# FYP_POWERBOARD_60V100A_REV2.net
KiCad netlist of a schematic drawn in Altium Designer
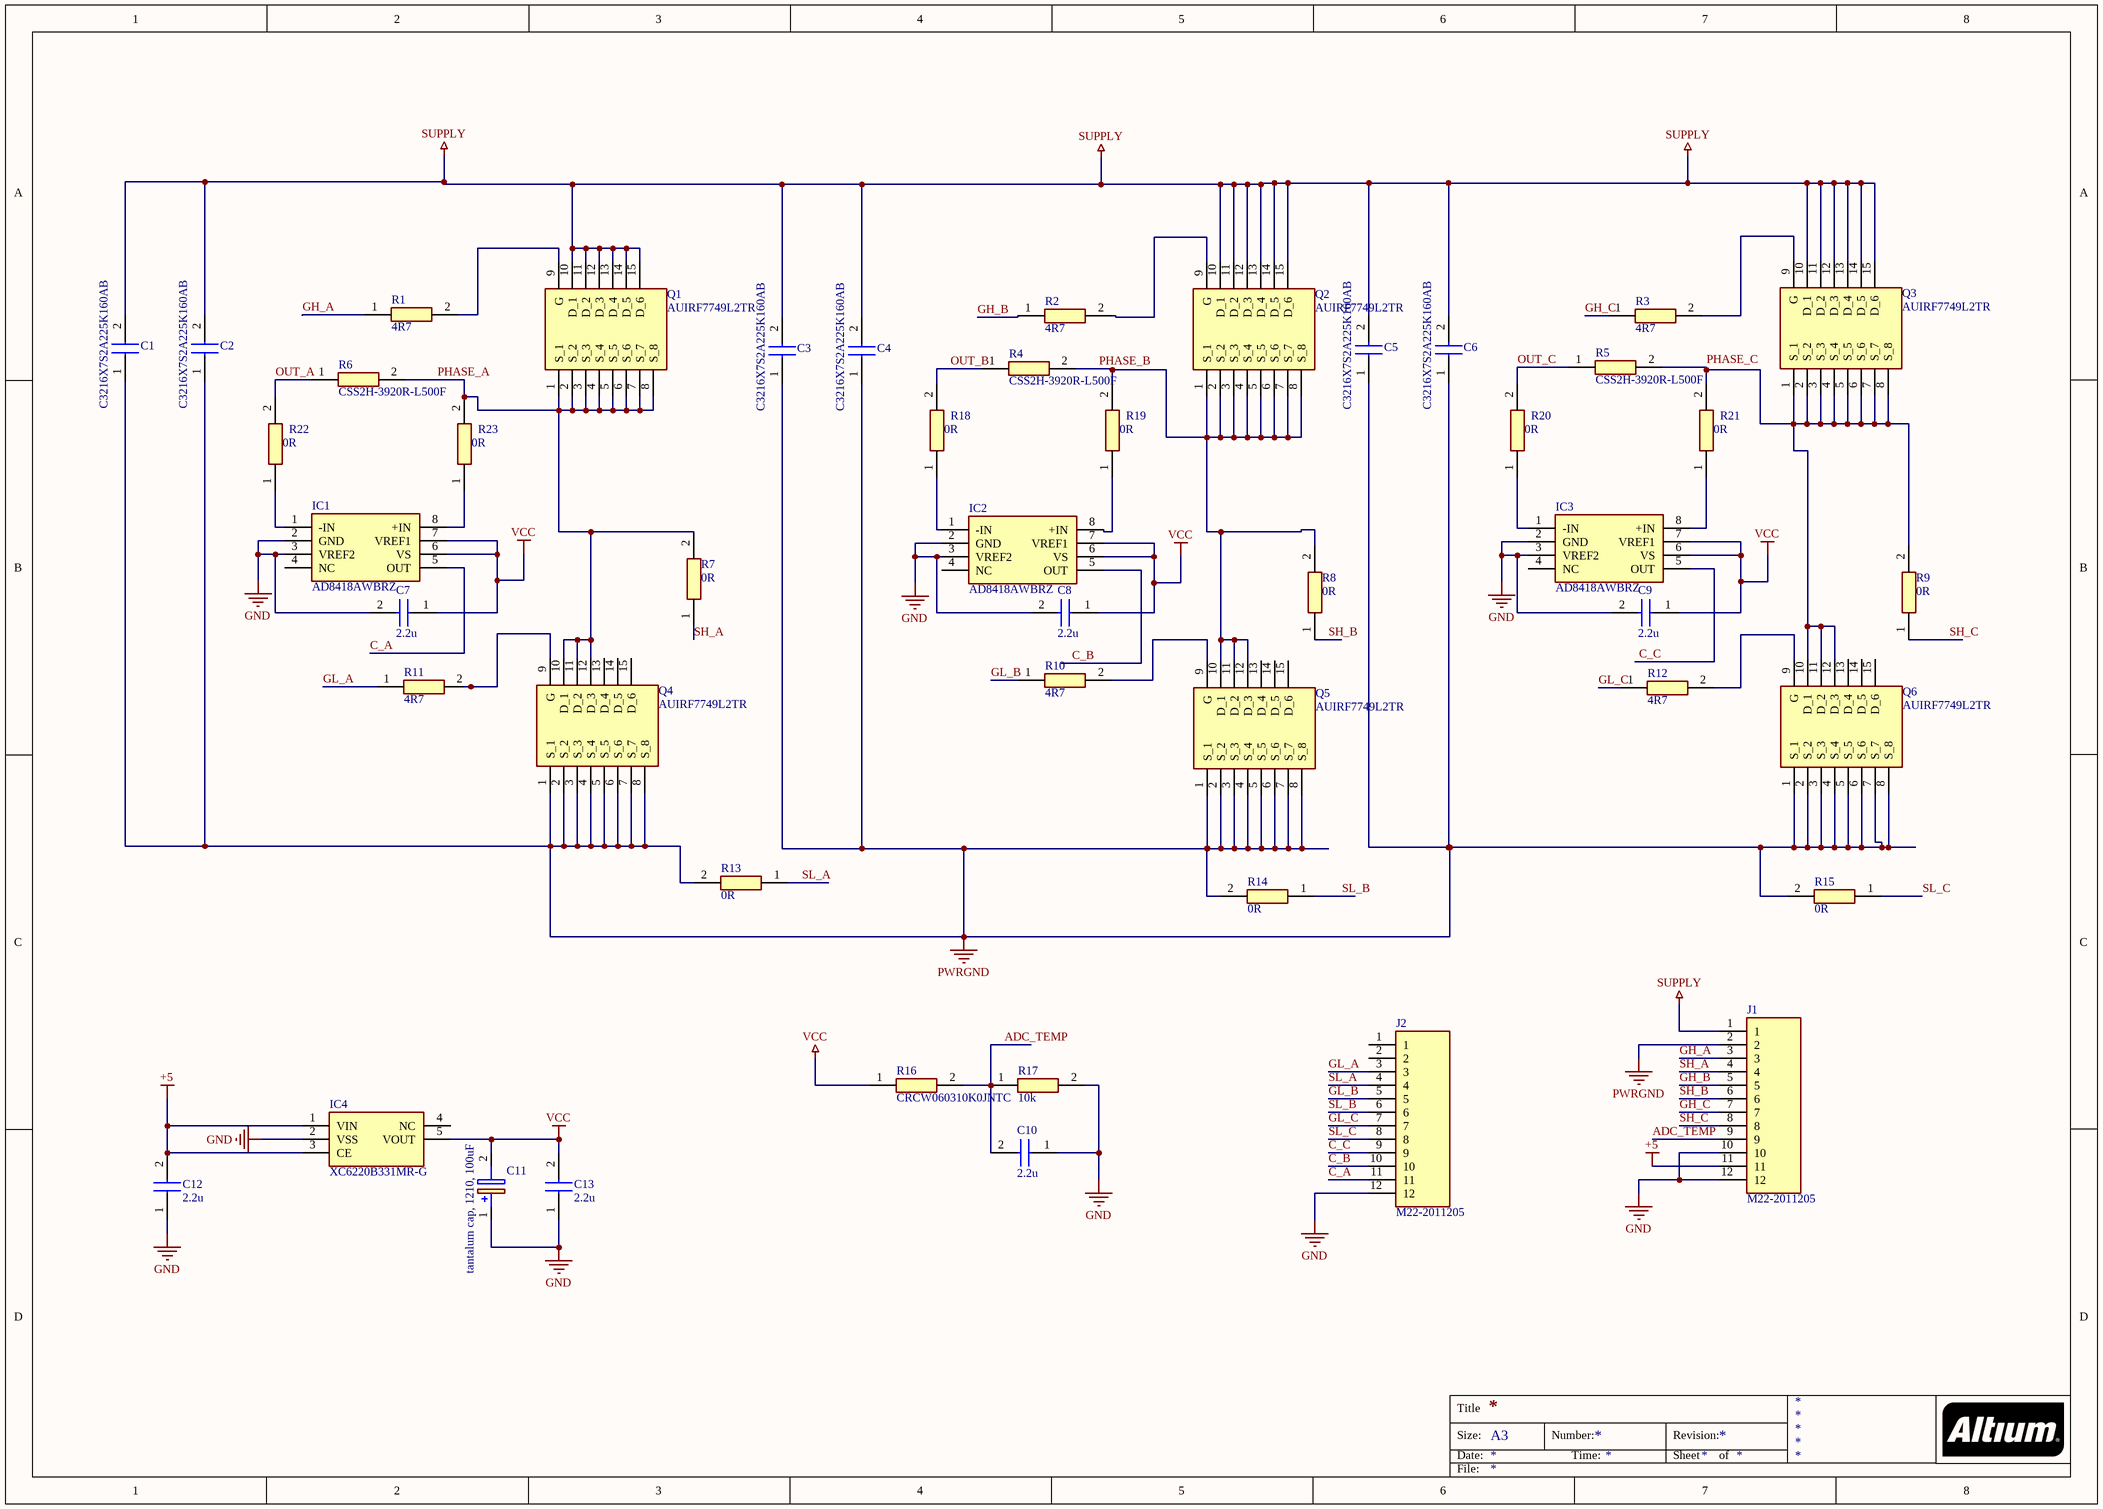
[diagram p0: FYP_POWERBOARD_60V100A_REV2.SchDoc]

(export (version "E")
  (design (tool "Eeschema 10.0.6"))
  (components
    (comp (ref "C1")
      (value "C3216X7S2A225K160AB")
      (footprint "SamacSys:CAPC3216X180N")
      (description "Capacitor")
      (fields
        (field (name "MOUSER PART NUMBER") "810-C3216X7S2A225K")
        (field (name "RS PART NUMBER") "7883079P")
      )
      (libsource (lib "*") (part "C3216X7S2A225K160AB"))
    )
    (comp (ref "C2")
      (value "C3216X7S2A225K160AB")
      (footprint "SamacSys:CAPC3216X180N")
      (description "Capacitor")
      (fields
        (field (name "MOUSER PART NUMBER") "810-C3216X7S2A225K")
        (field (name "RS PART NUMBER") "7883079P")
      )
      (libsource (lib "*") (part "C3216X7S2A225K160AB"))
    )
    (comp (ref "C3")
      (value "C3216X7S2A225K160AB")
      (footprint "SamacSys:CAPC3216X180N")
      (description "Capacitor")
      (fields
        (field (name "MOUSER PART NUMBER") "810-C3216X7S2A225K")
        (field (name "RS PART NUMBER") "7883079P")
      )
      (libsource (lib "*") (part "C3216X7S2A225K160AB"))
    )
    (comp (ref "C4")
      (value "C3216X7S2A225K160AB")
      (footprint "SamacSys:CAPC3216X180N")
      (description "Capacitor")
      (fields
        (field (name "MOUSER PART NUMBER") "810-C3216X7S2A225K")
        (field (name "RS PART NUMBER") "7883079P")
      )
      (libsource (lib "*") (part "C3216X7S2A225K160AB"))
    )
    (comp (ref "C5")
      (value "C3216X7S2A225K160AB")
      (footprint "SamacSys:CAPC3216X180N")
      (description "Capacitor")
      (fields
        (field (name "MOUSER PART NUMBER") "810-C3216X7S2A225K")
        (field (name "RS PART NUMBER") "7883079P")
      )
      (libsource (lib "*") (part "C3216X7S2A225K160AB"))
    )
    (comp (ref "C6")
      (value "C3216X7S2A225K160AB")
      (footprint "SamacSys:CAPC3216X180N")
      (description "Capacitor")
      (fields
        (field (name "MOUSER PART NUMBER") "810-C3216X7S2A225K")
        (field (name "RS PART NUMBER") "7883079P")
      )
      (libsource (lib "*") (part "C3216X7S2A225K160AB"))
    )
    (comp (ref "C7")
      (value "2.2u")
      (footprint "SamacSys:CAPC1608X90N")
      (description "Capacitor")
      (fields
        (field (name "MANUFACTURER_PART_NUMBER") "GCM188R70J225KE22D")
        (field (name "MOUSER PART NUMBER") "81-GCM188R70J225KE2D")
      )
      (libsource (lib "*") (part "GCM188R70J225KE22D"))
    )
    (comp (ref "C8")
      (value "2.2u")
      (footprint "SamacSys:CAPC1608X90N")
      (description "Capacitor")
      (fields
        (field (name "MANUFACTURER_PART_NUMBER") "GCM188R70J225KE22D")
        (field (name "MOUSER PART NUMBER") "81-GCM188R70J225KE2D")
      )
      (libsource (lib "*") (part "GCM188R70J225KE22D"))
    )
    (comp (ref "C9")
      (value "2.2u")
      (footprint "SamacSys:CAPC1608X90N")
      (description "Capacitor")
      (fields
        (field (name "MANUFACTURER_PART_NUMBER") "GCM188R70J225KE22D")
        (field (name "MOUSER PART NUMBER") "81-GCM188R70J225KE2D")
      )
      (libsource (lib "*") (part "GCM188R70J225KE22D"))
    )
    (comp (ref "C10")
      (value "2.2u")
      (footprint "SamacSys:CAPC1608X90N")
      (description "Capacitor")
      (fields
        (field (name "MANUFACTURER_PART_NUMBER") "GCM188R70J225KE22D")
        (field (name "MOUSER PART NUMBER") "81-GCM188R70J225KE2D")
      )
      (libsource (lib "*") (part "GCM188R70J225KE22D"))
    )
    (comp (ref "C11")
      (value "tantalum cap, 1210, 100uF")
      (footprint "SamacSys:CAPPM3528X210N")
      (description "Capacitor Polarised")
      (fields (field (name "MANUFACTURER_PART_NUMBER") "293D107X06R3B2TE3"))
      (libsource (lib "*") (part "293D107X06R3B2TE3"))
    )
    (comp (ref "C12")
      (value "2.2u")
      (footprint "SamacSys:CAPC1608X90N")
      (description "Capacitor")
      (fields
        (field (name "MANUFACTURER_PART_NUMBER") "GCM188R70J225KE22D")
        (field (name "MOUSER PART NUMBER") "81-GCM188R70J225KE2D")
      )
      (libsource (lib "*") (part "GCM188R70J225KE22D"))
    )
    (comp (ref "C13")
      (value "2.2u")
      (footprint "SamacSys:CAPC1608X90N")
      (description "Capacitor")
      (fields
        (field (name "MANUFACTURER_PART_NUMBER") "GCM188R70J225KE22D")
        (field (name "MOUSER PART NUMBER") "81-GCM188R70J225KE2D")
      )
      (libsource (lib "*") (part "GCM188R70J225KE22D"))
    )
    (comp (ref "IC1")
      (value "AD8418AWBRZ")
      (footprint "SamacSys:SOP65P490X110-8N")
      (description "Integrated Circuit")
      (fields (field (name "MOUSER PART NUMBER") "584-AD8418AWBRZ") (field (name "RS PART NUMBER") "7989903"))
      (libsource (lib "SamacSys") (part "AD8418AWBRZ"))
    )
    (comp (ref "IC2")
      (value "AD8418AWBRZ")
      (footprint "SamacSys:SOP65P490X110-8N")
      (description "Integrated Circuit")
      (fields (field (name "MOUSER PART NUMBER") "584-AD8418AWBRZ") (field (name "RS PART NUMBER") "7989903"))
      (libsource (lib "SamacSys") (part "AD8418AWBRZ"))
    )
    (comp (ref "IC3")
      (value "AD8418AWBRZ")
      (footprint "SamacSys:SOP65P490X110-8N")
      (description "Integrated Circuit")
      (fields (field (name "MOUSER PART NUMBER") "584-AD8418AWBRZ") (field (name "RS PART NUMBER") "7989903"))
      (libsource (lib "SamacSys") (part "AD8418AWBRZ"))
    )
    (comp (ref "IC4")
      (value "XC6220B331MR-G")
      (footprint "SamacSys:SOT95P280X120-5N")
      (description "Integrated Circuit")
      (fields (field (name "MOUSER PART NUMBER") "865-XC6220B331MR-G"))
      (libsource (lib "*") (part "XC6220B331MR-G"))
    )
    (comp (ref "J1")
      (value "M22-2011205")
      (footprint "SamacSys:HDRV12W60P0X200_1X12_2415X200X525P")
      (description "Connector")
      (fields (field (name "MOUSER PART NUMBER") "855-M22-2011205") (field (name "RS PART NUMBER") "1730943"))
      (libsource (lib "*") (part "M22-2011205"))
    )
    (comp (ref "J2")
      (value "M22-2011205")
      (footprint "SamacSys:HDRV12W60P0X200_1X12_2415X200X525P")
      (description "Connector")
      (fields (field (name "MOUSER PART NUMBER") "855-M22-2011205") (field (name "RS PART NUMBER") "1730943"))
      (libsource (lib "*") (part "M22-2011205"))
    )
    (comp (ref "Q1")
      (value "AUIRF7749L2TR")
      (footprint "SamacSys:IRF7749L2TRPBF")
      (description "MOSFET (N-Channel)")
      (fields (field (name "MOUSER PART NUMBER") "942-AUIRF7749L2TR"))
      (libsource (lib "*") (part "AUIRF7749L2TR"))
    )
    (comp (ref "Q2")
      (value "AUIRF7749L2TR")
      (footprint "SamacSys:IRF7749L2TRPBF")
      (description "MOSFET (N-Channel)")
      (fields (field (name "MOUSER PART NUMBER") "942-AUIRF7749L2TR"))
      (libsource (lib "*") (part "AUIRF7749L2TR"))
    )
    (comp (ref "Q3")
      (value "AUIRF7749L2TR")
      (footprint "SamacSys:IRF7749L2TRPBF")
      (description "MOSFET (N-Channel)")
      (fields (field (name "MOUSER PART NUMBER") "942-AUIRF7749L2TR"))
      (libsource (lib "*") (part "AUIRF7749L2TR"))
    )
    (comp (ref "Q4")
      (value "AUIRF7749L2TR")
      (footprint "SamacSys:IRF7749L2TRPBF")
      (description "MOSFET (N-Channel)")
      (fields (field (name "MOUSER PART NUMBER") "942-AUIRF7749L2TR"))
      (libsource (lib "*") (part "AUIRF7749L2TR"))
    )
    (comp (ref "Q5")
      (value "AUIRF7749L2TR")
      (footprint "SamacSys:IRF7749L2TRPBF")
      (description "MOSFET (N-Channel)")
      (fields (field (name "MOUSER PART NUMBER") "942-AUIRF7749L2TR"))
      (libsource (lib "*") (part "AUIRF7749L2TR"))
    )
    (comp (ref "Q6")
      (value "AUIRF7749L2TR")
      (footprint "SamacSys:IRF7749L2TRPBF")
      (description "MOSFET (N-Channel)")
      (fields (field (name "MOUSER PART NUMBER") "942-AUIRF7749L2TR"))
      (libsource (lib "*") (part "AUIRF7749L2TR"))
    )
    (comp (ref "R1")
      (value "4R7")
      (footprint "SamacSys:RESC1608X55N")
      (description "Resistor")
      (fields
        (field (name "MANUFACTURER_PART_NUMBER") "CPF0603B100RE")
        (field (name "MOUSER PART NUMBER") "279-CPF0603B100RE")
      )
      (libsource (lib "") (part "CPF0603B100RE_1"))
    )
    (comp (ref "R2")
      (value "4R7")
      (footprint "SamacSys:RESC1608X55N")
      (description "Resistor")
      (fields
        (field (name "MANUFACTURER_PART_NUMBER") "CPF0603B100RE")
        (field (name "MOUSER PART NUMBER") "279-CPF0603B100RE")
      )
      (libsource (lib "") (part "CPF0603B100RE_1"))
    )
    (comp (ref "R3")
      (value "4R7")
      (footprint "SamacSys:RESC1608X55N")
      (description "Resistor")
      (fields
        (field (name "MANUFACTURER_PART_NUMBER") "CPF0603B100RE")
        (field (name "MOUSER PART NUMBER") "279-CPF0603B100RE")
      )
      (libsource (lib "") (part "CPF0603B100RE_1"))
    )
    (comp (ref "R4")
      (value "CSS2H-3920R-L500F")
      (footprint "SamacSys:RESC10052X137N")
      (description "Resistor")
      (fields
        (field (name "MOUSER PART NUMBER") "652-CSS2H3920RL500F")
        (field (name "RS PART NUMBER") "1348150")
      )
      (libsource (lib "*") (part "CSS2H-3920R-L500F"))
    )
    (comp (ref "R5")
      (value "CSS2H-3920R-L500F")
      (footprint "SamacSys:RESC10052X137N")
      (description "Resistor")
      (fields
        (field (name "MOUSER PART NUMBER") "652-CSS2H3920RL500F")
        (field (name "RS PART NUMBER") "1348150")
      )
      (libsource (lib "*") (part "CSS2H-3920R-L500F"))
    )
    (comp (ref "R6")
      (value "CSS2H-3920R-L500F")
      (footprint "SamacSys:RESC10052X137N")
      (description "Resistor")
      (fields
        (field (name "MOUSER PART NUMBER") "652-CSS2H3920RL500F")
        (field (name "RS PART NUMBER") "1348150")
      )
      (libsource (lib "*") (part "CSS2H-3920R-L500F"))
    )
    (comp (ref "R7")
      (value "0R")
      (footprint "SamacSys:RESC1608X55N")
      (description "Resistor")
      (fields
        (field (name "MANUFACTURER_PART_NUMBER") "CPF0603B100RE")
        (field (name "MOUSER PART NUMBER") "279-CPF0603B100RE")
      )
      (libsource (lib "") (part "CPF0603B100RE_2"))
    )
    (comp (ref "R8")
      (value "0R")
      (footprint "SamacSys:RESC1608X55N")
      (description "Resistor")
      (fields
        (field (name "MANUFACTURER_PART_NUMBER") "CPF0603B100RE")
        (field (name "MOUSER PART NUMBER") "279-CPF0603B100RE")
      )
      (libsource (lib "") (part "CPF0603B100RE_2"))
    )
    (comp (ref "R9")
      (value "0R")
      (footprint "SamacSys:RESC1608X55N")
      (description "Resistor")
      (fields
        (field (name "MANUFACTURER_PART_NUMBER") "CPF0603B100RE")
        (field (name "MOUSER PART NUMBER") "279-CPF0603B100RE")
      )
      (libsource (lib "") (part "CPF0603B100RE_2"))
    )
    (comp (ref "R10")
      (value "4R7")
      (footprint "SamacSys:RESC1608X55N")
      (description "Resistor")
      (fields
        (field (name "MANUFACTURER_PART_NUMBER") "CPF0603B100RE")
        (field (name "MOUSER PART NUMBER") "279-CPF0603B100RE")
      )
      (libsource (lib "") (part "CPF0603B100RE_1"))
    )
    (comp (ref "R11")
      (value "4R7")
      (footprint "SamacSys:RESC1608X55N")
      (description "Resistor")
      (fields
        (field (name "MANUFACTURER_PART_NUMBER") "CPF0603B100RE")
        (field (name "MOUSER PART NUMBER") "279-CPF0603B100RE")
      )
      (libsource (lib "") (part "CPF0603B100RE_1"))
    )
    (comp (ref "R12")
      (value "4R7")
      (footprint "SamacSys:RESC1608X55N")
      (description "Resistor")
      (fields
        (field (name "MANUFACTURER_PART_NUMBER") "CPF0603B100RE")
        (field (name "MOUSER PART NUMBER") "279-CPF0603B100RE")
      )
      (libsource (lib "") (part "CPF0603B100RE_1"))
    )
    (comp (ref "R13")
      (value "0R")
      (footprint "SamacSys:RESC1608X55N")
      (description "Resistor")
      (fields
        (field (name "MANUFACTURER_PART_NUMBER") "CPF0603B100RE")
        (field (name "MOUSER PART NUMBER") "279-CPF0603B100RE")
      )
      (libsource (lib "*") (part "CPF0603B100RE"))
    )
    (comp (ref "R14")
      (value "0R")
      (footprint "SamacSys:RESC1608X55N")
      (description "Resistor")
      (fields
        (field (name "MANUFACTURER_PART_NUMBER") "CPF0603B100RE")
        (field (name "MOUSER PART NUMBER") "279-CPF0603B100RE")
      )
      (libsource (lib "*") (part "CPF0603B100RE"))
    )
    (comp (ref "R15")
      (value "0R")
      (footprint "SamacSys:RESC1608X55N")
      (description "Resistor")
      (fields
        (field (name "MANUFACTURER_PART_NUMBER") "CPF0603B100RE")
        (field (name "MOUSER PART NUMBER") "279-CPF0603B100RE")
      )
      (libsource (lib "*") (part "CPF0603B100RE"))
    )
    (comp (ref "R16")
      (value "CRCW060310K0JNTC")
      (footprint "SamacSys:RESC1608X50N")
      (description "Resistor")
      (libsource (lib "*") (part "CRCW060310K0JNTC"))
    )
    (comp (ref "R17")
      (value "10k")
      (footprint "SamacSys:RESC1608X55N")
      (description "Resistor")
      (fields
        (field (name "MANUFACTURER_PART_NUMBER") "CPF0603B100RE")
        (field (name "MOUSER PART NUMBER") "279-CPF0603B100RE")
      )
      (libsource (lib "") (part "CPF0603B100RE_1"))
    )
    (comp (ref "R18")
      (value "0R")
      (footprint "SamacSys:RESC1608X55N")
      (description "Resistor")
      (fields
        (field (name "MANUFACTURER_PART_NUMBER") "CPF0603B100RE")
        (field (name "MOUSER PART NUMBER") "279-CPF0603B100RE")
      )
      (libsource (lib "") (part "CPF0603B100RE_2"))
    )
    (comp (ref "R19")
      (value "0R")
      (footprint "SamacSys:RESC1608X55N")
      (description "Resistor")
      (fields
        (field (name "MANUFACTURER_PART_NUMBER") "CPF0603B100RE")
        (field (name "MOUSER PART NUMBER") "279-CPF0603B100RE")
      )
      (libsource (lib "") (part "CPF0603B100RE_2"))
    )
    (comp (ref "R20")
      (value "0R")
      (footprint "SamacSys:RESC1608X55N")
      (description "Resistor")
      (fields
        (field (name "MANUFACTURER_PART_NUMBER") "CPF0603B100RE")
        (field (name "MOUSER PART NUMBER") "279-CPF0603B100RE")
      )
      (libsource (lib "") (part "CPF0603B100RE_2"))
    )
    (comp (ref "R21")
      (value "0R")
      (footprint "SamacSys:RESC1608X55N")
      (description "Resistor")
      (fields
        (field (name "MANUFACTURER_PART_NUMBER") "CPF0603B100RE")
        (field (name "MOUSER PART NUMBER") "279-CPF0603B100RE")
      )
      (libsource (lib "") (part "CPF0603B100RE_2"))
    )
    (comp (ref "R22")
      (value "0R")
      (footprint "SamacSys:RESC1608X55N")
      (description "Resistor")
      (fields
        (field (name "MANUFACTURER_PART_NUMBER") "CPF0603B100RE")
        (field (name "MOUSER PART NUMBER") "279-CPF0603B100RE")
      )
      (libsource (lib "") (part "CPF0603B100RE_2"))
    )
    (comp (ref "R23")
      (value "0R")
      (footprint "SamacSys:RESC1608X55N")
      (description "Resistor")
      (fields
        (field (name "MANUFACTURER_PART_NUMBER") "CPF0603B100RE")
        (field (name "MOUSER PART NUMBER") "279-CPF0603B100RE")
      )
      (libsource (lib "") (part "CPF0603B100RE_2"))
    )
  )
  (nets
    (net (code "1") (name "+5") (class "Default")
      (node (ref "C12") (pin "2") (pinfunction "2_2") (pintype "passive"))
      (node (ref "IC4") (pin "1") (pinfunction "VIN_1") (pintype "passive"))
      (node (ref "IC4") (pin "3") (pinfunction "CE_3") (pintype "passive"))
      (node (ref "J1") (pin "11") (pinfunction "11_11") (pintype "passive"))
    )
    (net (code "2") (name "/ADC_TEMP") (class "Default")
      (node (ref "C10") (pin "2") (pinfunction "2_2") (pintype "passive"))
      (node (ref "J1") (pin "9") (pinfunction "9_9") (pintype "passive"))
      (node (ref "R16") (pin "2") (pinfunction "2_2") (pintype "passive"))
      (node (ref "R17") (pin "1") (pinfunction "1_1") (pintype "passive"))
    )
    (net (code "3") (name "/C_A") (class "Default")
      (node (ref "IC1") (pin "5") (pinfunction "OUT_5") (pintype "passive"))
      (node (ref "J2") (pin "11") (pinfunction "11_11") (pintype "passive"))
    )
    (net (code "4") (name "/C_B") (class "Default")
      (node (ref "IC2") (pin "5") (pinfunction "OUT_5") (pintype "passive"))
      (node (ref "J2") (pin "10") (pinfunction "10_10") (pintype "passive"))
    )
    (net (code "5") (name "/C_C") (class "Default")
      (node (ref "IC3") (pin "5") (pinfunction "OUT_5") (pintype "passive"))
      (node (ref "J2") (pin "9") (pinfunction "9_9") (pintype "passive"))
    )
    (net (code "6") (name "/GH_A") (class "Default")
      (node (ref "J1") (pin "3") (pinfunction "3_3") (pintype "passive"))
      (node (ref "R1") (pin "1") (pinfunction "1_1") (pintype "passive"))
    )
    (net (code "7") (name "/GH_B") (class "Default")
      (node (ref "J1") (pin "5") (pinfunction "5_5") (pintype "passive"))
      (node (ref "R2") (pin "1") (pinfunction "1_1") (pintype "passive"))
    )
    (net (code "8") (name "/GH_C") (class "Default")
      (node (ref "J1") (pin "7") (pinfunction "7_7") (pintype "passive"))
      (node (ref "R3") (pin "1") (pinfunction "1_1") (pintype "passive"))
    )
    (net (code "9") (name "/GL_A") (class "Default")
      (node (ref "J2") (pin "3") (pinfunction "3_3") (pintype "passive"))
      (node (ref "R11") (pin "1") (pinfunction "1_1") (pintype "passive"))
    )
    (net (code "10") (name "/GL_B") (class "Default")
      (node (ref "J2") (pin "5") (pinfunction "5_5") (pintype "passive"))
      (node (ref "R10") (pin "1") (pinfunction "1_1") (pintype "passive"))
    )
    (net (code "11") (name "/GL_C") (class "Default")
      (node (ref "J2") (pin "7") (pinfunction "7_7") (pintype "passive"))
      (node (ref "R12") (pin "1") (pinfunction "1_1") (pintype "passive"))
    )
    (net (code "12") (name "/OUT_A") (class "Default")
      (node (ref "R22") (pin "2") (pinfunction "2_2") (pintype "passive"))
      (node (ref "R6") (pin "1") (pinfunction "1_1") (pintype "passive"))
    )
    (net (code "13") (name "/OUT_B") (class "Default")
      (node (ref "R18") (pin "2") (pinfunction "2_2") (pintype "passive"))
      (node (ref "R4") (pin "1") (pinfunction "1_1") (pintype "passive"))
    )
    (net (code "14") (name "/OUT_C") (class "Default")
      (node (ref "R20") (pin "2") (pinfunction "2_2") (pintype "passive"))
      (node (ref "R5") (pin "1") (pinfunction "1_1") (pintype "passive"))
    )
    (net (code "15") (name "/PHASE_A") (class "Default")
      (node (ref "Q1") (pin "1") (pinfunction "S_1_1") (pintype "passive"))
      (node (ref "Q1") (pin "2") (pinfunction "S_2_2") (pintype "passive"))
      (node (ref "Q1") (pin "3") (pinfunction "S_3_3") (pintype "passive"))
      (node (ref "Q1") (pin "4") (pinfunction "S_4_4") (pintype "passive"))
      (node (ref "Q1") (pin "5") (pinfunction "S_5_5") (pintype "passive"))
      (node (ref "Q1") (pin "6") (pinfunction "S_6_6") (pintype "passive"))
      (node (ref "Q1") (pin "7") (pinfunction "S_7_7") (pintype "passive"))
      (node (ref "Q1") (pin "8") (pinfunction "S_8_8") (pintype "passive"))
      (node (ref "Q4") (pin "10") (pinfunction "D_1_10") (pintype "passive"))
      (node (ref "Q4") (pin "11") (pinfunction "D_2_11") (pintype "passive"))
      (node (ref "Q4") (pin "12") (pinfunction "D_3_12") (pintype "passive"))
      (node (ref "R23") (pin "2") (pinfunction "2_2") (pintype "passive"))
      (node (ref "R6") (pin "2") (pinfunction "2_2") (pintype "passive"))
      (node (ref "R7") (pin "2") (pinfunction "2_2") (pintype "passive"))
    )
    (net (code "16") (name "/PHASE_B") (class "Default")
      (node (ref "Q2") (pin "1") (pinfunction "S_1_1") (pintype "passive"))
      (node (ref "Q2") (pin "2") (pinfunction "S_2_2") (pintype "passive"))
      (node (ref "Q2") (pin "3") (pinfunction "S_3_3") (pintype "passive"))
      (node (ref "Q2") (pin "4") (pinfunction "S_4_4") (pintype "passive"))
      (node (ref "Q2") (pin "5") (pinfunction "S_5_5") (pintype "passive"))
      (node (ref "Q2") (pin "6") (pinfunction "S_6_6") (pintype "passive"))
      (node (ref "Q2") (pin "7") (pinfunction "S_7_7") (pintype "passive"))
      (node (ref "Q2") (pin "8") (pinfunction "S_8_8") (pintype "passive"))
      (node (ref "Q5") (pin "10") (pinfunction "D_1_10") (pintype "passive"))
      (node (ref "Q5") (pin "11") (pinfunction "D_2_11") (pintype "passive"))
      (node (ref "Q5") (pin "12") (pinfunction "D_3_12") (pintype "passive"))
      (node (ref "R19") (pin "2") (pinfunction "2_2") (pintype "passive"))
      (node (ref "R4") (pin "2") (pinfunction "2_2") (pintype "passive"))
      (node (ref "R8") (pin "2") (pinfunction "2_2") (pintype "passive"))
    )
    (net (code "17") (name "/PHASE_C") (class "Default")
      (node (ref "Q3") (pin "1") (pinfunction "S_1_1") (pintype "passive"))
      (node (ref "Q3") (pin "2") (pinfunction "S_2_2") (pintype "passive"))
      (node (ref "Q3") (pin "3") (pinfunction "S_3_3") (pintype "passive"))
      (node (ref "Q3") (pin "4") (pinfunction "S_4_4") (pintype "passive"))
      (node (ref "Q3") (pin "5") (pinfunction "S_5_5") (pintype "passive"))
      (node (ref "Q3") (pin "6") (pinfunction "S_6_6") (pintype "passive"))
      (node (ref "Q3") (pin "7") (pinfunction "S_7_7") (pintype "passive"))
      (node (ref "Q3") (pin "8") (pinfunction "S_8_8") (pintype "passive"))
      (node (ref "Q6") (pin "10") (pinfunction "D_1_10") (pintype "passive"))
      (node (ref "Q6") (pin "11") (pinfunction "D_2_11") (pintype "passive"))
      (node (ref "Q6") (pin "12") (pinfunction "D_3_12") (pintype "passive"))
      (node (ref "R21") (pin "2") (pinfunction "2_2") (pintype "passive"))
      (node (ref "R5") (pin "2") (pinfunction "2_2") (pintype "passive"))
      (node (ref "R9") (pin "2") (pinfunction "2_2") (pintype "passive"))
    )
    (net (code "18") (name "/SH_A") (class "Default")
      (node (ref "J1") (pin "4") (pinfunction "4_4") (pintype "passive"))
      (node (ref "R7") (pin "1") (pinfunction "1_1") (pintype "passive"))
    )
    (net (code "19") (name "/SH_B") (class "Default")
      (node (ref "J1") (pin "6") (pinfunction "6_6") (pintype "passive"))
      (node (ref "R8") (pin "1") (pinfunction "1_1") (pintype "passive"))
    )
    (net (code "20") (name "/SH_C") (class "Default")
      (node (ref "J1") (pin "8") (pinfunction "8_8") (pintype "passive"))
      (node (ref "R9") (pin "1") (pinfunction "1_1") (pintype "passive"))
    )
    (net (code "21") (name "/SL_A") (class "Default")
      (node (ref "J2") (pin "4") (pinfunction "4_4") (pintype "passive"))
      (node (ref "R13") (pin "1") (pinfunction "1_1") (pintype "passive"))
    )
    (net (code "22") (name "/SL_B") (class "Default")
      (node (ref "J2") (pin "6") (pinfunction "6_6") (pintype "passive"))
      (node (ref "R14") (pin "1") (pinfunction "1_1") (pintype "passive"))
    )
    (net (code "23") (name "/SL_C") (class "Default")
      (node (ref "J2") (pin "8") (pinfunction "8_8") (pintype "passive"))
      (node (ref "R15") (pin "1") (pinfunction "1_1") (pintype "passive"))
    )
    (net (code "24") (name "GND") (class "Default")
      (node (ref "C10") (pin "1") (pinfunction "1_1") (pintype "passive"))
      (node (ref "C11") (pin "1") (pinfunction "+_1") (pintype "passive"))
      (node (ref "C12") (pin "1") (pinfunction "1_1") (pintype "passive"))
      (node (ref "C13") (pin "1") (pinfunction "1_1") (pintype "passive"))
      (node (ref "C7") (pin "2") (pinfunction "2_2") (pintype "passive"))
      (node (ref "C8") (pin "2") (pinfunction "2_2") (pintype "passive"))
      (node (ref "C9") (pin "2") (pinfunction "2_2") (pintype "passive"))
      (node (ref "IC1") (pin "2") (pinfunction "GND_2") (pintype "passive"))
      (node (ref "IC1") (pin "3") (pinfunction "VREF2_3") (pintype "passive"))
      (node (ref "IC2") (pin "2") (pinfunction "GND_2") (pintype "passive"))
      (node (ref "IC2") (pin "3") (pinfunction "VREF2_3") (pintype "passive"))
      (node (ref "IC3") (pin "2") (pinfunction "GND_2") (pintype "passive"))
      (node (ref "IC3") (pin "3") (pinfunction "VREF2_3") (pintype "passive"))
      (node (ref "IC4") (pin "2") (pinfunction "VSS_2") (pintype "passive"))
      (node (ref "J1") (pin "10") (pinfunction "10_10") (pintype "passive"))
      (node (ref "J1") (pin "12") (pinfunction "12_12") (pintype "passive"))
      (node (ref "J2") (pin "12") (pinfunction "12_12") (pintype "passive"))
      (node (ref "R17") (pin "2") (pinfunction "2_2") (pintype "passive"))
    )
    (net (code "25") (name "Net-(IC1-+IN)") (class "Default")
      (node (ref "IC1") (pin "8") (pinfunction "+IN_8") (pintype "passive"))
      (node (ref "R23") (pin "1") (pinfunction "1_1") (pintype "passive"))
    )
    (net (code "26") (name "Net-(IC1--IN)") (class "Default")
      (node (ref "IC1") (pin "1") (pinfunction "-IN_1") (pintype "passive"))
      (node (ref "R22") (pin "1") (pinfunction "1_1") (pintype "passive"))
    )
    (net (code "27") (name "Net-(IC2-+IN)") (class "Default")
      (node (ref "IC2") (pin "8") (pinfunction "+IN_8") (pintype "passive"))
      (node (ref "R19") (pin "1") (pinfunction "1_1") (pintype "passive"))
    )
    (net (code "28") (name "Net-(IC2--IN)") (class "Default")
      (node (ref "IC2") (pin "1") (pinfunction "-IN_1") (pintype "passive"))
      (node (ref "R18") (pin "1") (pinfunction "1_1") (pintype "passive"))
    )
    (net (code "29") (name "Net-(IC3-+IN)") (class "Default")
      (node (ref "IC3") (pin "8") (pinfunction "+IN_8") (pintype "passive"))
      (node (ref "R21") (pin "1") (pinfunction "1_1") (pintype "passive"))
    )
    (net (code "30") (name "Net-(IC3--IN)") (class "Default")
      (node (ref "IC3") (pin "1") (pinfunction "-IN_1") (pintype "passive"))
      (node (ref "R20") (pin "1") (pinfunction "1_1") (pintype "passive"))
    )
    (net (code "31") (name "Net-(Q1-G)") (class "Default")
      (node (ref "Q1") (pin "9") (pinfunction "G_9") (pintype "passive"))
      (node (ref "R1") (pin "2") (pinfunction "2_2") (pintype "passive"))
    )
    (net (code "32") (name "Net-(Q2-G)") (class "Default")
      (node (ref "Q2") (pin "9") (pinfunction "G_9") (pintype "passive"))
      (node (ref "R2") (pin "2") (pinfunction "2_2") (pintype "passive"))
    )
    (net (code "33") (name "Net-(Q3-G)") (class "Default")
      (node (ref "Q3") (pin "9") (pinfunction "G_9") (pintype "passive"))
      (node (ref "R3") (pin "2") (pinfunction "2_2") (pintype "passive"))
    )
    (net (code "34") (name "Net-(Q4-G)") (class "Default")
      (node (ref "Q4") (pin "9") (pinfunction "G_9") (pintype "passive"))
      (node (ref "R11") (pin "2") (pinfunction "2_2") (pintype "passive"))
    )
    (net (code "35") (name "Net-(Q5-G)") (class "Default")
      (node (ref "Q5") (pin "9") (pinfunction "G_9") (pintype "passive"))
      (node (ref "R10") (pin "2") (pinfunction "2_2") (pintype "passive"))
    )
    (net (code "36") (name "Net-(Q6-G)") (class "Default")
      (node (ref "Q6") (pin "9") (pinfunction "G_9") (pintype "passive"))
      (node (ref "R12") (pin "2") (pinfunction "2_2") (pintype "passive"))
    )
    (net (code "37") (name "PWRGND") (class "Default")
      (node (ref "C1") (pin "1") (pinfunction "1_1") (pintype "passive"))
      (node (ref "C2") (pin "1") (pinfunction "1_1") (pintype "passive"))
      (node (ref "C3") (pin "1") (pinfunction "1_1") (pintype "passive"))
      (node (ref "C4") (pin "1") (pinfunction "1_1") (pintype "passive"))
      (node (ref "C5") (pin "1") (pinfunction "1_1") (pintype "passive"))
      (node (ref "C6") (pin "1") (pinfunction "1_1") (pintype "passive"))
      (node (ref "J1") (pin "2") (pinfunction "2_2") (pintype "passive"))
      (node (ref "Q4") (pin "1") (pinfunction "S_1_1") (pintype "passive"))
      (node (ref "Q4") (pin "2") (pinfunction "S_2_2") (pintype "passive"))
      (node (ref "Q4") (pin "3") (pinfunction "S_3_3") (pintype "passive"))
      (node (ref "Q4") (pin "4") (pinfunction "S_4_4") (pintype "passive"))
      (node (ref "Q4") (pin "5") (pinfunction "S_5_5") (pintype "passive"))
      (node (ref "Q4") (pin "6") (pinfunction "S_6_6") (pintype "passive"))
      (node (ref "Q4") (pin "7") (pinfunction "S_7_7") (pintype "passive"))
      (node (ref "Q4") (pin "8") (pinfunction "S_8_8") (pintype "passive"))
      (node (ref "Q5") (pin "1") (pinfunction "S_1_1") (pintype "passive"))
      (node (ref "Q5") (pin "2") (pinfunction "S_2_2") (pintype "passive"))
      (node (ref "Q5") (pin "3") (pinfunction "S_3_3") (pintype "passive"))
      (node (ref "Q5") (pin "4") (pinfunction "S_4_4") (pintype "passive"))
      (node (ref "Q5") (pin "5") (pinfunction "S_5_5") (pintype "passive"))
      (node (ref "Q5") (pin "6") (pinfunction "S_6_6") (pintype "passive"))
      (node (ref "Q5") (pin "7") (pinfunction "S_7_7") (pintype "passive"))
      (node (ref "Q5") (pin "8") (pinfunction "S_8_8") (pintype "passive"))
      (node (ref "Q6") (pin "1") (pinfunction "S_1_1") (pintype "passive"))
      (node (ref "Q6") (pin "2") (pinfunction "S_2_2") (pintype "passive"))
      (node (ref "Q6") (pin "3") (pinfunction "S_3_3") (pintype "passive"))
      (node (ref "Q6") (pin "4") (pinfunction "S_4_4") (pintype "passive"))
      (node (ref "Q6") (pin "5") (pinfunction "S_5_5") (pintype "passive"))
      (node (ref "Q6") (pin "6") (pinfunction "S_6_6") (pintype "passive"))
      (node (ref "Q6") (pin "7") (pinfunction "S_7_7") (pintype "passive"))
      (node (ref "Q6") (pin "8") (pinfunction "S_8_8") (pintype "passive"))
      (node (ref "R13") (pin "2") (pinfunction "2_2") (pintype "passive"))
      (node (ref "R14") (pin "2") (pinfunction "2_2") (pintype "passive"))
      (node (ref "R15") (pin "2") (pinfunction "2_2") (pintype "passive"))
    )
    (net (code "38") (name "SUPPLY") (class "Default")
      (node (ref "C1") (pin "2") (pinfunction "2_2") (pintype "passive"))
      (node (ref "C2") (pin "2") (pinfunction "2_2") (pintype "passive"))
      (node (ref "C3") (pin "2") (pinfunction "2_2") (pintype "passive"))
      (node (ref "C4") (pin "2") (pinfunction "2_2") (pintype "passive"))
      (node (ref "C5") (pin "2") (pinfunction "2_2") (pintype "passive"))
      (node (ref "C6") (pin "2") (pinfunction "2_2") (pintype "passive"))
      (node (ref "J1") (pin "1") (pinfunction "1_1") (pintype "passive"))
      (node (ref "Q1") (pin "10") (pinfunction "D_1_10") (pintype "passive"))
      (node (ref "Q1") (pin "11") (pinfunction "D_2_11") (pintype "passive"))
      (node (ref "Q1") (pin "12") (pinfunction "D_3_12") (pintype "passive"))
      (node (ref "Q1") (pin "13") (pinfunction "D_4_13") (pintype "passive"))
      (node (ref "Q1") (pin "14") (pinfunction "D_5_14") (pintype "passive"))
      (node (ref "Q1") (pin "15") (pinfunction "D_6_15") (pintype "passive"))
      (node (ref "Q2") (pin "10") (pinfunction "D_1_10") (pintype "passive"))
      (node (ref "Q2") (pin "11") (pinfunction "D_2_11") (pintype "passive"))
      (node (ref "Q2") (pin "12") (pinfunction "D_3_12") (pintype "passive"))
      (node (ref "Q2") (pin "13") (pinfunction "D_4_13") (pintype "passive"))
      (node (ref "Q2") (pin "14") (pinfunction "D_5_14") (pintype "passive"))
      (node (ref "Q2") (pin "15") (pinfunction "D_6_15") (pintype "passive"))
      (node (ref "Q3") (pin "10") (pinfunction "D_1_10") (pintype "passive"))
      (node (ref "Q3") (pin "11") (pinfunction "D_2_11") (pintype "passive"))
      (node (ref "Q3") (pin "12") (pinfunction "D_3_12") (pintype "passive"))
      (node (ref "Q3") (pin "13") (pinfunction "D_4_13") (pintype "passive"))
      (node (ref "Q3") (pin "14") (pinfunction "D_5_14") (pintype "passive"))
      (node (ref "Q3") (pin "15") (pinfunction "D_6_15") (pintype "passive"))
    )
    (net (code "39") (name "VCC") (class "Default")
      (node (ref "C11") (pin "2") (pinfunction "-_2") (pintype "passive"))
      (node (ref "C13") (pin "2") (pinfunction "2_2") (pintype "passive"))
      (node (ref "C7") (pin "1") (pinfunction "1_1") (pintype "passive"))
      (node (ref "C8") (pin "1") (pinfunction "1_1") (pintype "passive"))
      (node (ref "C9") (pin "1") (pinfunction "1_1") (pintype "passive"))
      (node (ref "IC1") (pin "6") (pinfunction "VS_6") (pintype "passive"))
      (node (ref "IC1") (pin "7") (pinfunction "VREF1_7") (pintype "passive"))
      (node (ref "IC2") (pin "6") (pinfunction "VS_6") (pintype "passive"))
      (node (ref "IC2") (pin "7") (pinfunction "VREF1_7") (pintype "passive"))
      (node (ref "IC3") (pin "6") (pinfunction "VS_6") (pintype "passive"))
      (node (ref "IC3") (pin "7") (pinfunction "VREF1_7") (pintype "passive"))
      (node (ref "IC4") (pin "5") (pinfunction "VOUT_5") (pintype "passive"))
      (node (ref "R16") (pin "1") (pinfunction "1_1") (pintype "passive"))
    )
    (net (code "40") (name "unconnected-(IC1-NC-Pad4)") (class "Default")
      (node (ref "IC1") (pin "4") (pinfunction "NC_4") (pintype "passive"))
    )
    (net (code "41") (name "unconnected-(IC2-NC-Pad4)") (class "Default")
      (node (ref "IC2") (pin "4") (pinfunction "NC_4") (pintype "passive"))
    )
    (net (code "42") (name "unconnected-(IC3-NC-Pad4)") (class "Default")
      (node (ref "IC3") (pin "4") (pinfunction "NC_4") (pintype "passive"))
    )
    (net (code "43") (name "unconnected-(IC4-NC-Pad4)") (class "Default")
      (node (ref "IC4") (pin "4") (pinfunction "NC_4") (pintype "passive"))
    )
    (net (code "44") (name "unconnected-(J2-Pad1)") (class "Default")
      (node (ref "J2") (pin "1") (pinfunction "1_1") (pintype "passive"))
    )
    (net (code "45") (name "unconnected-(J2-Pad2)") (class "Default")
      (node (ref "J2") (pin "2") (pinfunction "2_2") (pintype "passive"))
    )
    (net (code "46") (name "unconnected-(Q4-D_4-Pad13)") (class "Default")
      (node (ref "Q4") (pin "13") (pinfunction "D_4_13") (pintype "passive"))
    )
    (net (code "47") (name "unconnected-(Q4-D_5-Pad14)") (class "Default")
      (node (ref "Q4") (pin "14") (pinfunction "D_5_14") (pintype "passive"))
    )
    (net (code "48") (name "unconnected-(Q4-D_6-Pad15)") (class "Default")
      (node (ref "Q4") (pin "15") (pinfunction "D_6_15") (pintype "passive"))
    )
    (net (code "49") (name "unconnected-(Q5-D_4-Pad13)") (class "Default")
      (node (ref "Q5") (pin "13") (pinfunction "D_4_13") (pintype "passive"))
    )
    (net (code "50") (name "unconnected-(Q5-D_5-Pad14)") (class "Default")
      (node (ref "Q5") (pin "14") (pinfunction "D_5_14") (pintype "passive"))
    )
    (net (code "51") (name "unconnected-(Q5-D_6-Pad15)") (class "Default")
      (node (ref "Q5") (pin "15") (pinfunction "D_6_15") (pintype "passive"))
    )
    (net (code "52") (name "unconnected-(Q6-D_4-Pad13)") (class "Default")
      (node (ref "Q6") (pin "13") (pinfunction "D_4_13") (pintype "passive"))
    )
    (net (code "53") (name "unconnected-(Q6-D_5-Pad14)") (class "Default")
      (node (ref "Q6") (pin "14") (pinfunction "D_5_14") (pintype "passive"))
    )
    (net (code "54") (name "unconnected-(Q6-D_6-Pad15)") (class "Default")
      (node (ref "Q6") (pin "15") (pinfunction "D_6_15") (pintype "passive"))
    )
  )
)
